# Audio_Amplifier.net
KiCad netlist of a schematic drawn in Altium Designer
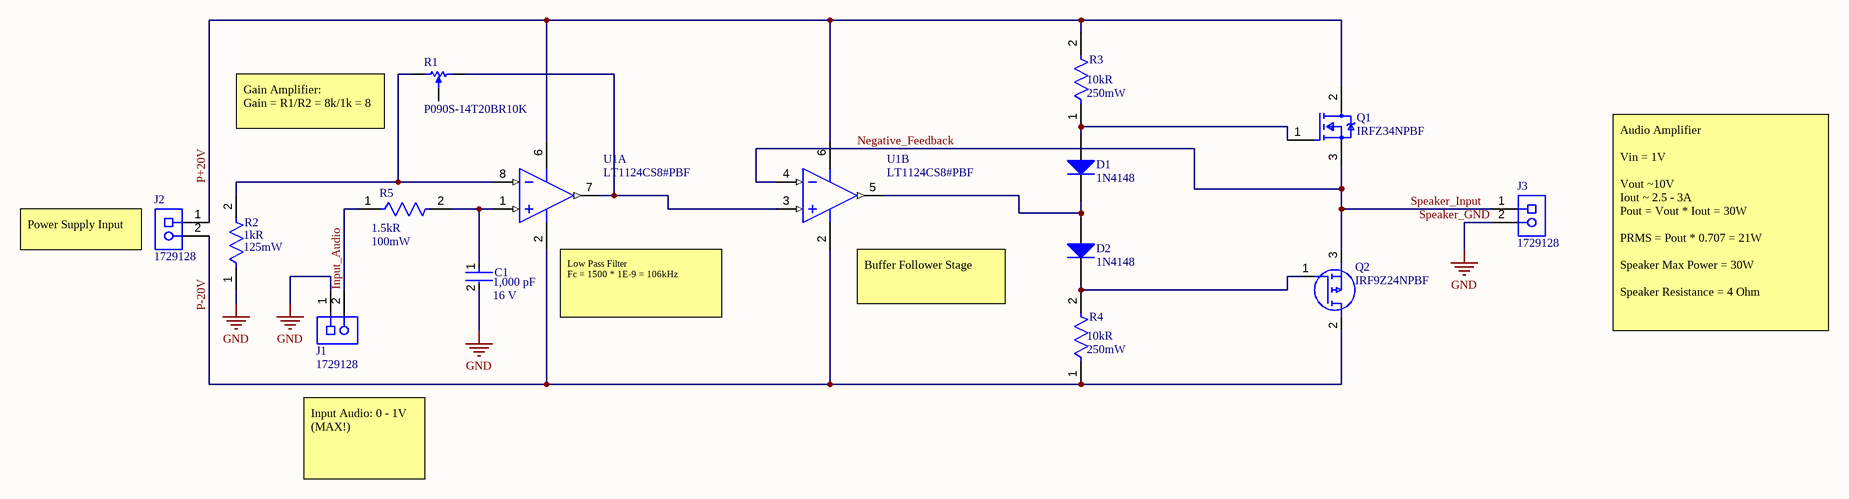
[diagram p0: Audio_Amplifier.SchDoc]

(export (version "E")
  (design (tool "Eeschema 10.0.6"))
  (components
    (comp (ref "C1")
      (value "C1206C102K4RACTU")
      (footprint "FP-C1206C-EB-MFG")
      (description "CAP CER 1000PF 16V 10% X7R 1206")
      (fields
        (field (name "CAPACITANCE") "1,000 pF")
        (field (name "VOLTAGE RATING") "16 V")
        (field (name "OCTOPART") "https://octopart.com/c1206c102k4ractu-kemet-19050577")
        (field (name "MANUFACTURER") "KEMET")
      )
      (libsource (lib "Altium Content Vault") (part "b4654b650e69147ec39a6b967a45e02"))
    )
    (comp (ref "D1")
      (value "1N4148")
      (footprint "NXP-SOD27-2_V")
      (description "High-speed Diode, 100 V, 450 mA, 2-Pin SOD27, RoHS")
      (fields (field (name "MANUFACTURER") "NXP Semiconductors"))
      (libsource (lib "Altium Content Vault") (part "NXP-A1K2-2"))
    )
    (comp (ref "D2")
      (value "1N4148")
      (footprint "NXP-SOD27-2_V")
      (description "High-speed Diode, 100 V, 450 mA, 2-Pin SOD27, RoHS")
      (fields (field (name "MANUFACTURER") "NXP Semiconductors"))
      (libsource (lib "Altium Content Vault") (part "NXP-A1K2-2"))
    )
    (comp (ref "J1")
      (value "1729128")
      (footprint "PHOE-1729128-2_V")
      (description "PCB Terminal Block, 13.5 A, 400 V, 2-Pin THD, RoHS, Bulk")
      (fields (field (name "MANUFACTURER") "Phoenix Contact"))
      (libsource (lib "") (part "CN-2P-F-R2_2"))
    )
    (comp (ref "J2")
      (value "1729128")
      (footprint "PHOE-1729128-2_V")
      (description "PCB Terminal Block, 13.5 A, 400 V, 2-Pin THD, RoHS, Bulk")
      (fields (field (name "MANUFACTURER") "Phoenix Contact"))
      (libsource (lib "Altium Content Vault") (part "CN-2P-F-R2"))
    )
    (comp (ref "J3")
      (value "1729128")
      (footprint "PHOE-1729128-2_V")
      (description "PCB Terminal Block, 13.5 A, 400 V, 2-Pin THD, RoHS, Bulk")
      (fields (field (name "MANUFACTURER") "Phoenix Contact"))
      (libsource (lib "") (part "CN-2P-F-R2_1"))
    )
    (comp (ref "Q1")
      (value "IRFZ34NPBF")
      (footprint "FP-PG-TO220-3-MFG")
      (description "MOSFET N-CH 55V 29A TO220AB")
      (libsource (lib "Altium Content Vault") (part "8b62d417cbef8344eebe0bde0c45977"))
    )
    (comp (ref "Q2")
      (value "IRF9Z24NPBF")
      (footprint "TO254P469X1042X1967-3P")
      (description "Infineon IRF9Z24NPBF P-channel MOSFET Transistor, 12 A, 55 V, 3-Pin TO-220AB")
      (fields (field (name "MOUSER PART NUMBER") "942-IRF9Z24NPBF"))
      (libsource (lib "McMaster University - MAC Formula Electric") (part "IRF9Z24NPBF"))
    )
    (comp (ref "R1")
      (value "P090S-14T20BR10K")
      (footprint "RES-POT-3")
      (fields (field (name "TOLERANCE") "±20%") (field (name "MANUFACTURER") "BI Technologies"))
      (libsource (lib "Altium Content Vault") (part "RES-ADJ-3_A"))
    )
    (comp (ref "R2")
      (value "RC2012F102CS")
      (footprint "FP-RC2012-MFG")
      (description "Res Thick Film 0805 1kΩ 1% 0.125W ±100ppm/°C Molded SMD T/R")
      (fields
        (field (name "MAX POWER DISSIPATION") "125mW")
        (field (name "RESISTANCE") "1kR")
        (field (name "TOLERANCE") "1%")
      )
      (libsource (lib "Altium Content Vault") (part "1029c3af85768c4190bb7ad29bc67b5"))
    )
    (comp (ref "R3")
      (value "CRCW120610K0FKEA")
      (footprint "FP-CRCW1206-e3-IPC_C")
      (description "RES Thick Film, 10kΩ, 1%, 0.25W, 100ppm/°C, 1206")
      (fields
        (field (name "MAX POWER DISSIPATION") "250mW")
        (field (name "TOLERANCE") "1%")
        (field (name "RESISTANCE") "10kR")
      )
      (libsource (lib "Altium Content Vault") (part "1029c3af85768c4190bb7ad29bc67b5"))
    )
    (comp (ref "R4")
      (value "CRCW120610K0FKEA")
      (footprint "FP-CRCW1206-e3-IPC_C")
      (description "RES Thick Film, 10kΩ, 1%, 0.25W, 100ppm/°C, 1206")
      (fields
        (field (name "MAX POWER DISSIPATION") "250mW")
        (field (name "TOLERANCE") "1%")
        (field (name "RESISTANCE") "10kR")
      )
      (libsource (lib "Altium Content Vault") (part "1029c3af85768c4190bb7ad29bc67b5"))
    )
    (comp (ref "R5")
      (value "RC1608F1501CS")
      (footprint "FP-RC1608-IPC_B")
      (description "Res Thick Film 0603 1.5kΩ 1% 0.1W ±100ppm/°C Molded SMD T/R")
      (fields
        (field (name "RESISTANCE") "1.5kR")
        (field (name "TOLERANCE") "1%")
        (field (name "POWER RATING") "100mW")
      )
      (libsource (lib "Altium Content Vault") (part "1029c3af85768c4190bb7ad29bc67b5"))
    )
    (comp (ref "U1")
      (value "LT1124CS8#PBF")
      (footprint "LT-S8-8_M")
      (fields
        (field (name "MANUFACTURER") "Linear Technology")
        (field (name "LINEAR TECHNOLOGY PART NUMBER") "LT1124-1")
      )
      (libsource (lib "Altium Content Vault") (part "LT-LT1124-S8-8"))
    )
  )
  (nets
    (net (code "1") (name "/Input_Audio") (class "Default")
      (node (ref "J1") (pin "2") (pinfunction "2_2") (pintype "passive"))
      (node (ref "R5") (pin "1") (pinfunction "1_1") (pintype "passive"))
    )
    (net (code "2") (name "/Negative_Feedback") (class "Default")
      (node (ref "J3") (pin "1") (pinfunction "1_1") (pintype "passive"))
      (node (ref "Q1") (pin "3") (pinfunction "SOURCE_3") (pintype "passive"))
      (node (ref "Q2") (pin "3") (pinfunction "S_3") (pintype "passive"))
      (node (ref "U1") (pin "4") (pinfunction "-IN_B_4") (pintype "input"))
    )
    (net (code "3") (name "/P+20V") (class "Default")
      (node (ref "J2") (pin "1") (pinfunction "1_1") (pintype "passive"))
      (node (ref "Q1") (pin "2") (pinfunction "DRAIN_2") (pintype "passive"))
      (node (ref "R3") (pin "2") (pinfunction "2_2") (pintype "passive"))
      (node (ref "U1") (pin "6") (pinfunction "V+_6") (pintype "power_in"))
    )
    (net (code "4") (name "/P-20V") (class "Default")
      (node (ref "J2") (pin "2") (pinfunction "2_2") (pintype "passive"))
      (node (ref "Q2") (pin "2") (pinfunction "D_2") (pintype "passive"))
      (node (ref "R4") (pin "1") (pinfunction "1_1") (pintype "passive"))
      (node (ref "U1") (pin "2") (pinfunction "V-_2") (pintype "power_in"))
    )
    (net (code "5") (name "GND") (class "Default")
      (node (ref "C1") (pin "2") (pinfunction "2_2") (pintype "passive"))
      (node (ref "J1") (pin "1") (pinfunction "1_1") (pintype "passive"))
      (node (ref "J3") (pin "2") (pinfunction "2_2") (pintype "passive"))
      (node (ref "R2") (pin "1") (pinfunction "1_1") (pintype "passive"))
    )
    (net (code "6") (name "Net-(D1-A)") (class "Default")
      (node (ref "D1") (pin "1") (pinfunction "A_1") (pintype "passive"))
      (node (ref "Q1") (pin "1") (pinfunction "GATE_1") (pintype "passive"))
      (node (ref "R3") (pin "1") (pinfunction "1_1") (pintype "passive"))
    )
    (net (code "7") (name "Net-(D1-K)") (class "Default")
      (node (ref "D1") (pin "2") (pinfunction "K_2") (pintype "passive"))
      (node (ref "D2") (pin "1") (pinfunction "A_1") (pintype "passive"))
      (node (ref "U1") (pin "5") (pinfunction "OUT_B_5") (pintype "output"))
    )
    (net (code "8") (name "Net-(D2-K)") (class "Default")
      (node (ref "D2") (pin "2") (pinfunction "K_2") (pintype "passive"))
      (node (ref "Q2") (pin "1") (pinfunction "G_1") (pintype "passive"))
      (node (ref "R4") (pin "2") (pinfunction "2_2") (pintype "passive"))
    )
    (net (code "9") (name "Net-(U1A-+IN_A)") (class "Default")
      (node (ref "C1") (pin "1") (pinfunction "1_1") (pintype "passive"))
      (node (ref "R5") (pin "2") (pinfunction "2_2") (pintype "passive"))
      (node (ref "U1") (pin "1") (pinfunction "+IN_A_1") (pintype "input"))
    )
    (net (code "10") (name "Net-(U1A--IN_A)") (class "Default")
      (node (ref "R1") (pin "1") (pinfunction "1_1") (pintype "passive"))
      (node (ref "R2") (pin "2") (pinfunction "2_2") (pintype "passive"))
      (node (ref "U1") (pin "8") (pinfunction "-IN_A_8") (pintype "input"))
    )
    (net (code "11") (name "Net-(U1A-OUT_A)") (class "Default")
      (node (ref "R1") (pin "3") (pinfunction "3_3") (pintype "passive"))
      (node (ref "U1") (pin "3") (pinfunction "+IN_B_3") (pintype "input"))
      (node (ref "U1") (pin "7") (pinfunction "OUT_A_7") (pintype "output"))
    )
    (net (code "12") (name "unconnected-(R1-Pad2)") (class "Default")
      (node (ref "R1") (pin "2") (pinfunction "2_2") (pintype "passive"))
    )
  )
)
